# 2.net
KiCad netlist of a schematic drawn in Altium Designer
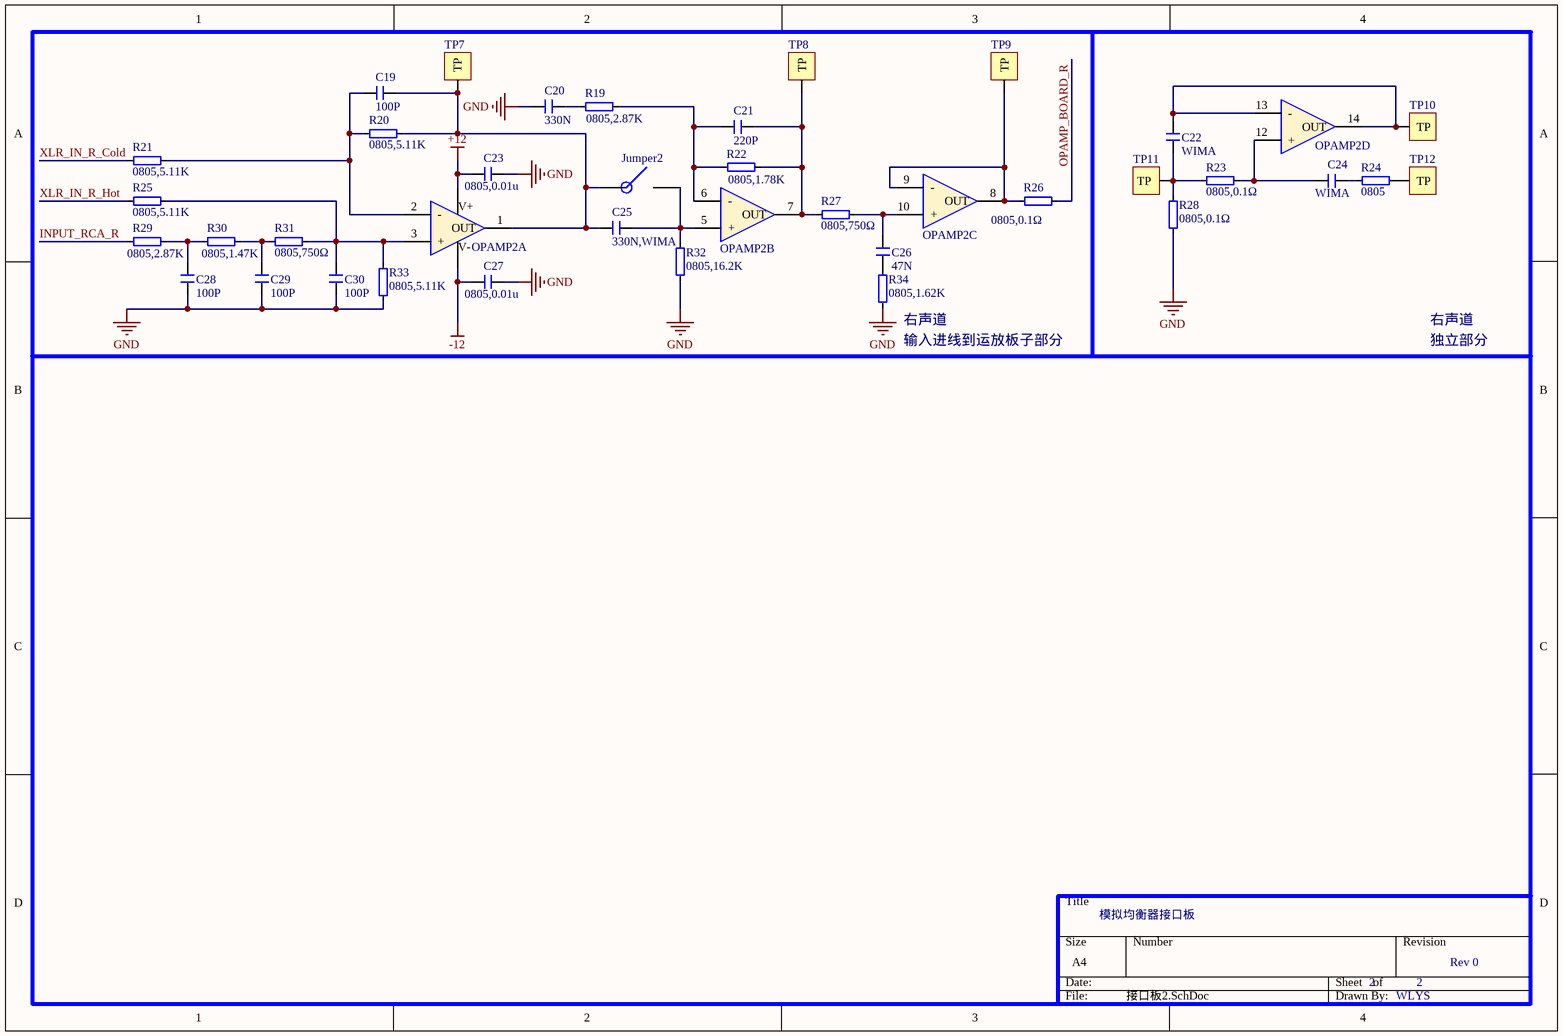
[diagram p0: 接口板2.SchDoc]

(export (version "E")
  (design (tool "Eeschema 10.0.6"))
  (components
    (comp (ref "C19") (value "100P") (footprint "WIMA_5mm") (libsource (lib "模拟均衡器") (part "WIMA_CAP_100P")))
    (comp (ref "C20")
      (value "330N")
      (footprint "WIMA_5mmPin*10mmL")
      (libsource (lib "模拟均衡器") (part "WIMA_CAP_330N"))
    )
    (comp (ref "C21") (value "220P") (footprint "WIMA_5mm") (libsource (lib "模拟均衡器") (part "WIMA_CAP_220P")))
    (comp (ref "C22") (value "WIMA") (footprint "WIMA_5mm") (libsource (lib "模拟均衡器") (part "WIMA_CAP_100P")))
    (comp (ref "C23") (value "0805,0.01u") (footprint "0805_C") (libsource (lib "模拟均衡器") (part "C0805")))
    (comp (ref "C24") (value "WIMA") (footprint "WIMA_5mm") (libsource (lib "模拟均衡器") (part "WIMA_CAP_100P")))
    (comp (ref "C25")
      (value "330N,WIMA")
      (footprint "WIMA_5mmPin*10mmL")
      (libsource (lib "模拟均衡器") (part "WIMA_CAP_330N"))
    )
    (comp (ref "C26") (value "47N") (footprint "WIMA_5mm") (libsource (lib "模拟均衡器") (part "WIMA_CAP_47N")))
    (comp (ref "C27") (value "0805,0.01u") (footprint "0805_C") (libsource (lib "模拟均衡器") (part "C0805")))
    (comp (ref "C28") (value "100P") (footprint "WIMA_5mm") (libsource (lib "模拟均衡器") (part "WIMA_CAP_100P")))
    (comp (ref "C29") (value "100P") (footprint "WIMA_5mm") (libsource (lib "模拟均衡器") (part "WIMA_CAP_100P")))
    (comp (ref "C30") (value "100P") (footprint "WIMA_5mm") (libsource (lib "模拟均衡器") (part "WIMA_CAP_100P")))
    (comp (ref "Jumper2") (value "Jumper") (footprint "0805_J") (libsource (lib "模拟均衡器") (part "Jumper")))
    (comp (ref "OPAMP2")
      (value "4277UA")
      (footprint "SOIC-14_150mil")
      (libsource (lib "模拟均衡器") (part "OPA4277UA"))
    )
    (comp (ref "R19") (value "0805,2.87K") (footprint "0805_R") (libsource (lib "模拟均衡器") (part "R0805")))
    (comp (ref "R20") (value "0805,5.11K") (footprint "0805_R") (libsource (lib "模拟均衡器") (part "R0805")))
    (comp (ref "R21") (value "0805,5.11K") (footprint "0805_R") (libsource (lib "模拟均衡器") (part "R0805")))
    (comp (ref "R22") (value "0805,1.78K") (footprint "0805_R") (libsource (lib "模拟均衡器") (part "R0805")))
    (comp (ref "R23") (value "0805,0.1Ω") (footprint "0805_R") (libsource (lib "模拟均衡器") (part "R0805")))
    (comp (ref "R24") (value "0805") (footprint "0805_R") (libsource (lib "模拟均衡器") (part "R0805")))
    (comp (ref "R25") (value "0805,5.11K") (footprint "0805_R") (libsource (lib "模拟均衡器") (part "R0805")))
    (comp (ref "R26") (value "0805,0.1Ω") (footprint "0805_R") (libsource (lib "模拟均衡器") (part "R0805")))
    (comp (ref "R27") (value "0805,750Ω") (footprint "0805_R") (libsource (lib "模拟均衡器") (part "R0805")))
    (comp (ref "R28") (value "0805,0.1Ω") (footprint "0805_R") (libsource (lib "模拟均衡器") (part "R0805")))
    (comp (ref "R29") (value "0805,2.87K") (footprint "0805_R") (libsource (lib "模拟均衡器") (part "R0805")))
    (comp (ref "R30") (value "0805,1.47K") (footprint "0805_R") (libsource (lib "模拟均衡器") (part "R0805")))
    (comp (ref "R31") (value "0805,750Ω") (footprint "0805_R") (libsource (lib "模拟均衡器") (part "R0805")))
    (comp (ref "R32") (value "0805,16.2K") (footprint "0805_R") (libsource (lib "模拟均衡器") (part "R0805")))
    (comp (ref "R33") (value "0805,5.11K") (footprint "0805_R") (libsource (lib "模拟均衡器") (part "R0805")))
    (comp (ref "R34") (value "0805,1.62K") (footprint "0805_R") (libsource (lib "模拟均衡器") (part "R0805")))
    (comp (ref "TP7") (value "测试点") (footprint "TestPoint") (libsource (lib "") (part "测试点_1")))
    (comp (ref "TP8") (value "测试点") (footprint "TestPoint") (libsource (lib "") (part "测试点_1")))
    (comp (ref "TP9") (value "测试点") (footprint "TestPoint") (libsource (lib "") (part "测试点_1")))
    (comp (ref "TP10") (value "测试点") (footprint "TestPoint") (libsource (lib "模拟均衡器") (part "测试点")))
    (comp (ref "TP11") (value "测试点") (footprint "TestPoint") (libsource (lib "") (part "测试点_2")))
    (comp (ref "TP12") (value "测试点") (footprint "TestPoint") (libsource (lib "模拟均衡器") (part "测试点")))
  )
  (nets
    (net (code "1") (name "+12") (class "Default")
      (node (ref "C23") (pin "1") (pinfunction "1_1") (pintype "passive"))
      (node (ref "OPAMP2") (pin "4") (pinfunction "V+_4") (pintype "passive"))
    )
    (net (code "2") (name "-12") (class "Default")
      (node (ref "C27") (pin "1") (pinfunction "1_1") (pintype "passive"))
      (node (ref "OPAMP2") (pin "11") (pinfunction "V-_11") (pintype "passive"))
    )
    (net (code "3") (name "/INPUT_RCA_R") (class "Default")
      (node (ref "R29") (pin "1") (pinfunction "1_1") (pintype "passive"))
    )
    (net (code "4") (name "/OPAMP_BOARD_R") (class "Default")
      (node (ref "R26") (pin "2") (pinfunction "2_2") (pintype "passive"))
    )
    (net (code "5") (name "/XLR_IN_R_Cold") (class "Default")
      (node (ref "R21") (pin "2") (pinfunction "2_2") (pintype "passive"))
    )
    (net (code "6") (name "/XLR_IN_R_Hot") (class "Default")
      (node (ref "R25") (pin "2") (pinfunction "2_2") (pintype "passive"))
    )
    (net (code "7") (name "GND") (class "Default")
      (node (ref "C20") (pin "1") (pinfunction "1_1") (pintype "passive"))
      (node (ref "C23") (pin "2") (pinfunction "2_2") (pintype "passive"))
      (node (ref "C27") (pin "2") (pinfunction "2_2") (pintype "passive"))
      (node (ref "C28") (pin "2") (pinfunction "2_2") (pintype "passive"))
      (node (ref "C29") (pin "2") (pinfunction "2_2") (pintype "passive"))
      (node (ref "C30") (pin "2") (pinfunction "2_2") (pintype "passive"))
      (node (ref "R28") (pin "2") (pinfunction "2_2") (pintype "passive"))
      (node (ref "R32") (pin "1") (pinfunction "1_1") (pintype "passive"))
      (node (ref "R33") (pin "1") (pinfunction "1_1") (pintype "passive"))
      (node (ref "R34") (pin "1") (pinfunction "1_1") (pintype "passive"))
    )
    (net (code "8") (name "Net-(C20-Pad2)") (class "Default")
      (node (ref "C20") (pin "2") (pinfunction "2_2") (pintype "passive"))
      (node (ref "R19") (pin "1") (pinfunction "1_1") (pintype "passive"))
    )
    (net (code "9") (name "Net-(C24-Pad2)") (class "Default")
      (node (ref "C24") (pin "2") (pinfunction "2_2") (pintype "passive"))
      (node (ref "R24") (pin "2") (pinfunction "2_2") (pintype "passive"))
    )
    (net (code "10") (name "Net-(C26-Pad2)") (class "Default")
      (node (ref "C26") (pin "2") (pinfunction "2_2") (pintype "passive"))
      (node (ref "R34") (pin "2") (pinfunction "2_2") (pintype "passive"))
    )
    (net (code "11") (name "Net-(C28-Pad1)") (class "Default")
      (node (ref "C28") (pin "1") (pinfunction "1_1") (pintype "passive"))
      (node (ref "R29") (pin "2") (pinfunction "2_2") (pintype "passive"))
      (node (ref "R30") (pin "1") (pinfunction "1_1") (pintype "passive"))
    )
    (net (code "12") (name "Net-(C29-Pad1)") (class "Default")
      (node (ref "C29") (pin "1") (pinfunction "1_1") (pintype "passive"))
      (node (ref "R30") (pin "2") (pinfunction "2_2") (pintype "passive"))
      (node (ref "R31") (pin "1") (pinfunction "1_1") (pintype "passive"))
    )
    (net (code "13") (name "Net-(OPAMP2A-+)") (class "Default")
      (node (ref "C30") (pin "1") (pinfunction "1_1") (pintype "passive"))
      (node (ref "OPAMP2") (pin "3") (pinfunction "+_3") (pintype "passive"))
      (node (ref "R25") (pin "1") (pinfunction "1_1") (pintype "passive"))
      (node (ref "R31") (pin "2") (pinfunction "2_2") (pintype "passive"))
      (node (ref "R33") (pin "2") (pinfunction "2_2") (pintype "passive"))
    )
    (net (code "14") (name "Net-(OPAMP2A--)") (class "Default")
      (node (ref "C19") (pin "1") (pinfunction "1_1") (pintype "passive"))
      (node (ref "OPAMP2") (pin "2") (pinfunction "-_2") (pintype "passive"))
      (node (ref "R20") (pin "1") (pinfunction "1_1") (pintype "passive"))
      (node (ref "R21") (pin "1") (pinfunction "1_1") (pintype "passive"))
    )
    (net (code "15") (name "Net-(OPAMP2A-OUT)") (class "Default")
      (node (ref "C19") (pin "2") (pinfunction "2_2") (pintype "passive"))
      (node (ref "C25") (pin "1") (pinfunction "1_1") (pintype "passive"))
      (node (ref "Jumper2") (pin "1") (pinfunction "1_1") (pintype "passive"))
      (node (ref "OPAMP2") (pin "1") (pinfunction "OUT_1") (pintype "passive"))
      (node (ref "R20") (pin "2") (pinfunction "2_2") (pintype "passive"))
      (node (ref "TP7") (pin "1") (pinfunction "TP_1") (pintype "passive"))
    )
    (net (code "16") (name "Net-(OPAMP2B-+)") (class "Default")
      (node (ref "C25") (pin "2") (pinfunction "2_2") (pintype "passive"))
      (node (ref "Jumper2") (pin "2") (pinfunction "2_2") (pintype "passive"))
      (node (ref "OPAMP2") (pin "5") (pinfunction "+_5") (pintype "passive"))
      (node (ref "R32") (pin "2") (pinfunction "2_2") (pintype "passive"))
    )
    (net (code "17") (name "Net-(OPAMP2B--)") (class "Default")
      (node (ref "C21") (pin "1") (pinfunction "1_1") (pintype "passive"))
      (node (ref "OPAMP2") (pin "6") (pinfunction "-_6") (pintype "passive"))
      (node (ref "R19") (pin "2") (pinfunction "2_2") (pintype "passive"))
      (node (ref "R22") (pin "1") (pinfunction "1_1") (pintype "passive"))
    )
    (net (code "18") (name "Net-(OPAMP2B-OUT)") (class "Default")
      (node (ref "C21") (pin "2") (pinfunction "2_2") (pintype "passive"))
      (node (ref "OPAMP2") (pin "7") (pinfunction "OUT_7") (pintype "passive"))
      (node (ref "R22") (pin "2") (pinfunction "2_2") (pintype "passive"))
      (node (ref "R27") (pin "1") (pinfunction "1_1") (pintype "passive"))
      (node (ref "TP8") (pin "1") (pinfunction "TP_1") (pintype "passive"))
    )
    (net (code "19") (name "Net-(OPAMP2C-+)") (class "Default")
      (node (ref "C26") (pin "1") (pinfunction "1_1") (pintype "passive"))
      (node (ref "OPAMP2") (pin "10") (pinfunction "+_10") (pintype "passive"))
      (node (ref "R27") (pin "2") (pinfunction "2_2") (pintype "passive"))
    )
    (net (code "20") (name "Net-(OPAMP2C--)") (class "Default")
      (node (ref "OPAMP2") (pin "8") (pinfunction "OUT_8") (pintype "passive"))
      (node (ref "OPAMP2") (pin "9") (pinfunction "-_9") (pintype "passive"))
      (node (ref "R26") (pin "1") (pinfunction "1_1") (pintype "passive"))
      (node (ref "TP9") (pin "1") (pinfunction "TP_1") (pintype "passive"))
    )
    (net (code "21") (name "Net-(OPAMP2D-+)") (class "Default")
      (node (ref "C24") (pin "1") (pinfunction "1_1") (pintype "passive"))
      (node (ref "OPAMP2") (pin "12") (pinfunction "+_12") (pintype "passive"))
      (node (ref "R23") (pin "1") (pinfunction "1_1") (pintype "passive"))
    )
    (net (code "22") (name "Net-(OPAMP2D--)") (class "Default")
      (node (ref "C22") (pin "1") (pinfunction "1_1") (pintype "passive"))
      (node (ref "OPAMP2") (pin "13") (pinfunction "-_13") (pintype "passive"))
      (node (ref "OPAMP2") (pin "14") (pinfunction "OUT_14") (pintype "passive"))
      (node (ref "TP10") (pin "1") (pinfunction "TP_1") (pintype "passive"))
    )
    (net (code "23") (name "Net-(TP11-TP)") (class "Default")
      (node (ref "C22") (pin "2") (pinfunction "2_2") (pintype "passive"))
      (node (ref "R23") (pin "2") (pinfunction "2_2") (pintype "passive"))
      (node (ref "R28") (pin "1") (pinfunction "1_1") (pintype "passive"))
      (node (ref "TP11") (pin "1") (pinfunction "TP_1") (pintype "passive"))
    )
    (net (code "24") (name "Net-(TP12-TP)") (class "Default")
      (node (ref "R24") (pin "1") (pinfunction "1_1") (pintype "passive"))
      (node (ref "TP12") (pin "1") (pinfunction "TP_1") (pintype "passive"))
    )
  )
)
